# Slot.net
KiCad netlist of a schematic drawn in Altium Designer
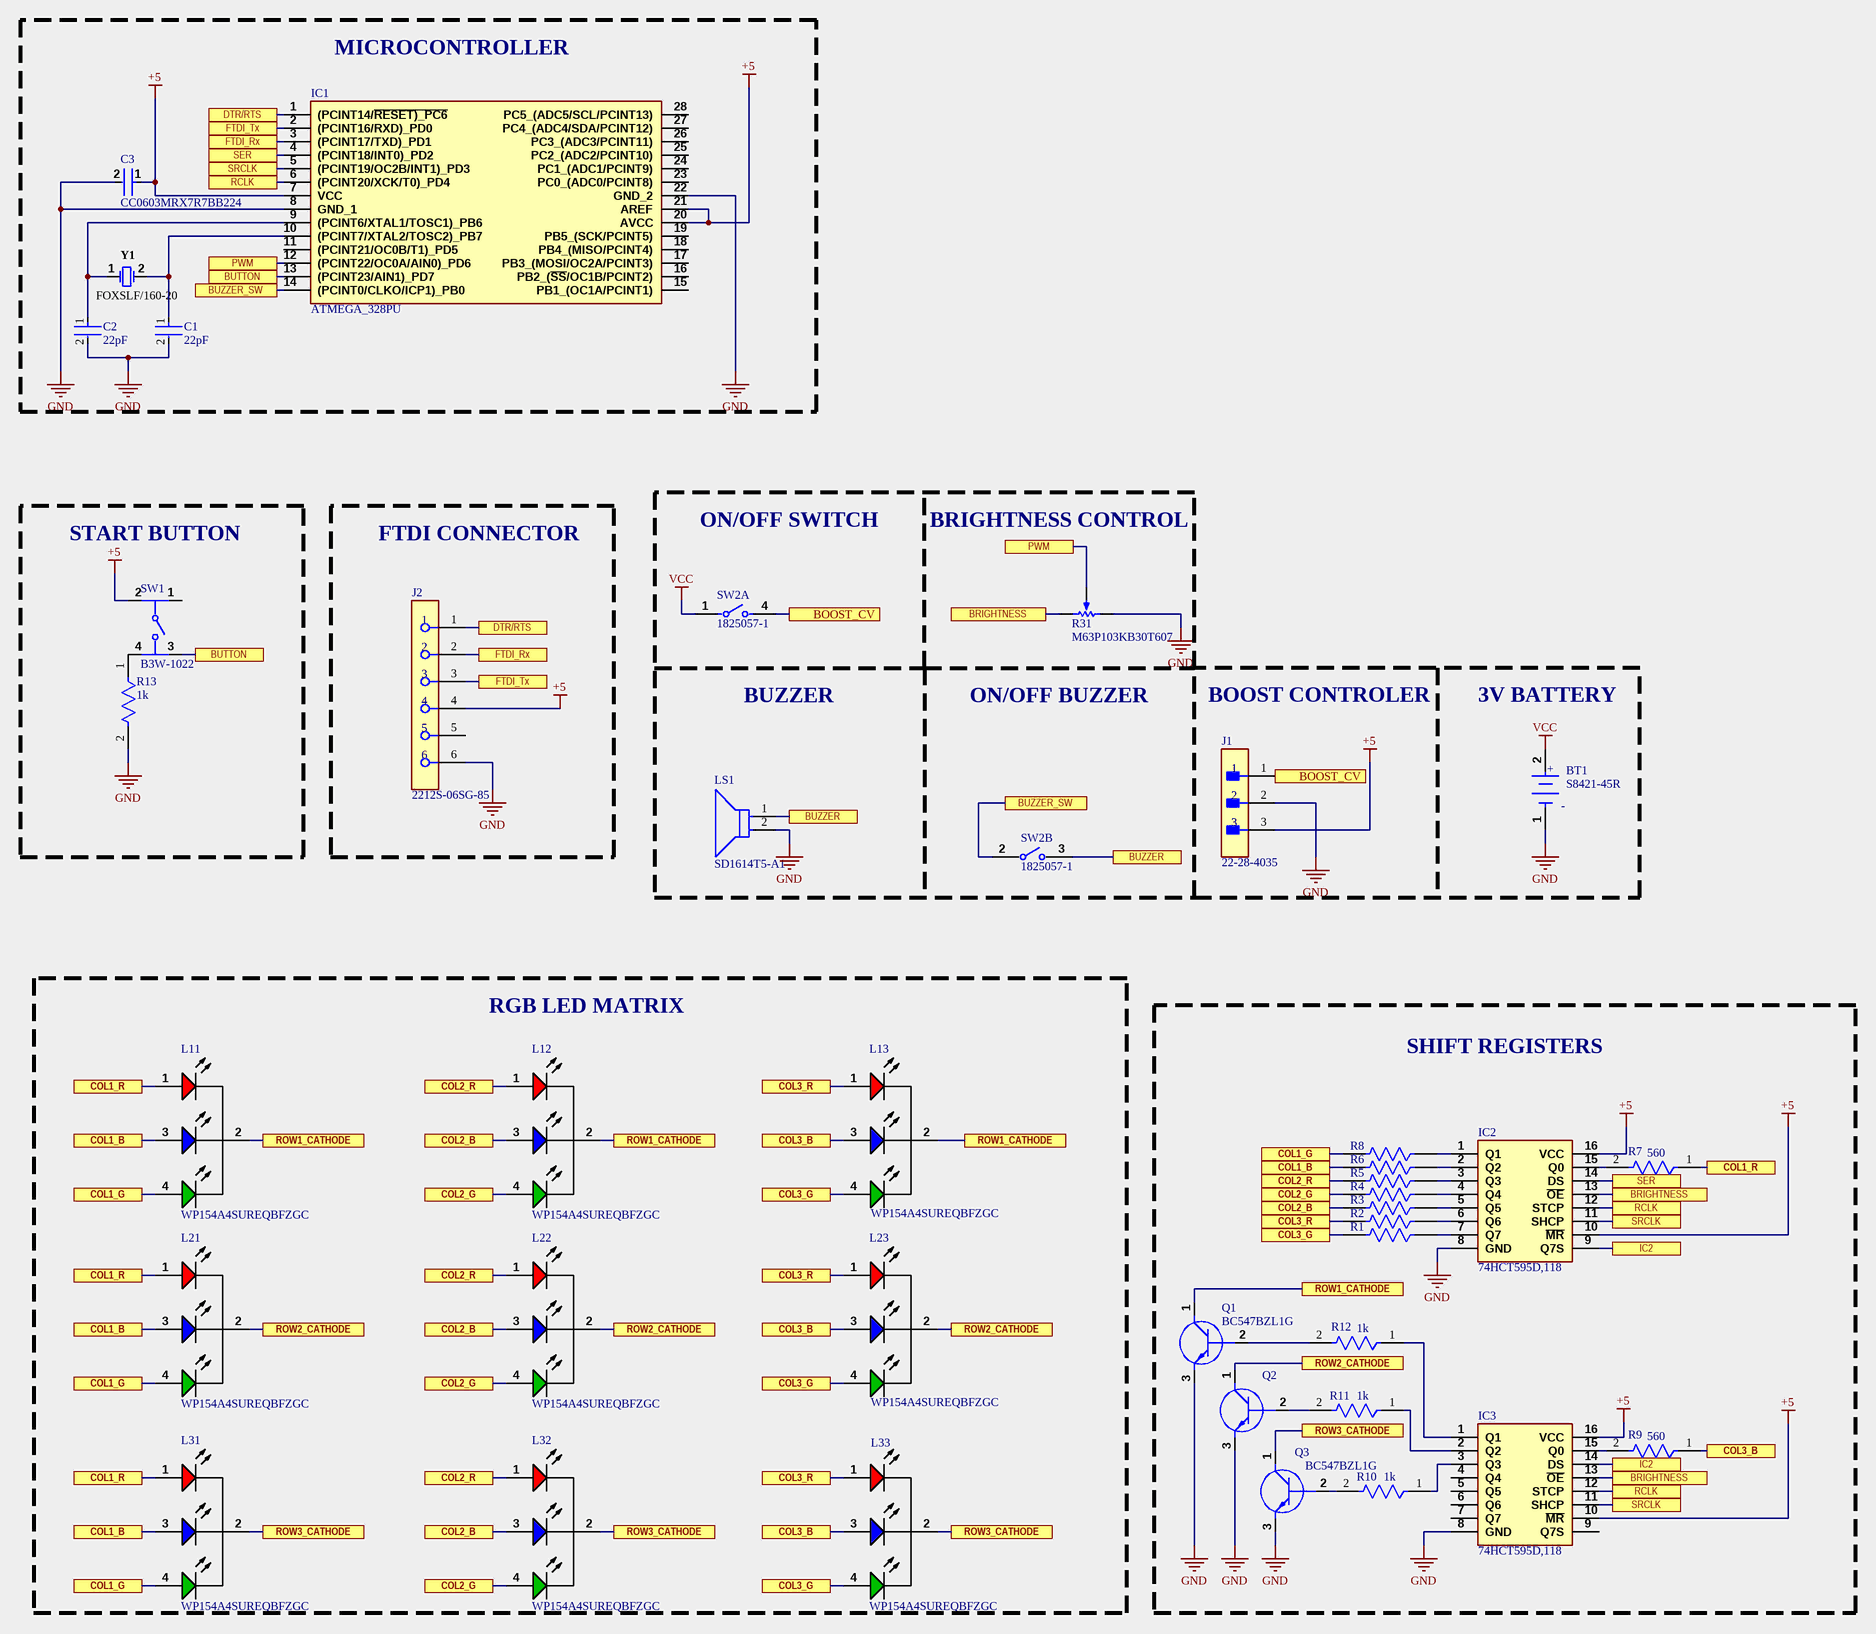
[diagram p0: Slot.SchDoc]

(export (version "E")
  (design (tool "Eeschema 10.0.6"))
  (components
    (comp (ref "BT1")
      (value "S8421-45R")
      (footprint "FP-S8421-45R-MFG")
      (description "BATTERY HOLDER COIN 20MM SMD")
      (libsource (lib "Altium Content Vault") (part "60d3b5b901a8747834971d0eb8cf3fd"))
    )
    (comp (ref "C1")
      (value "22pF")
      (footprint "FP-K221K15X7RF5TL2-MFG")
      (description "K221K15X7RF5TL2 Multilayer Ceramic Capacitor, 220 pF, 50 V, ± 10%, X7R, Radial Leaded")
      (fields (field (name "TOLERANCE") "10%"))
      (libsource (lib "Altium Content Vault") (part "b4654b650e69147ec39a6b967a45e02"))
    )
    (comp (ref "C2")
      (value "22pF")
      (footprint "FP-K221K15X7RF5TL2-MFG")
      (description "K221K15X7RF5TL2 Multilayer Ceramic Capacitor, 220 pF, 50 V, ± 10%, X7R, Radial Leaded")
      (fields (field (name "TOLERANCE") "10%"))
      (libsource (lib "Altium Content Vault") (part "b4654b650e69147ec39a6b967a45e02"))
    )
    (comp (ref "C3")
      (value "CC0603MRX7R7BB224")
      (footprint "FP-CC0603-DA-MFG")
      (description "CAP CER 0.22UF 16V X7R 0603")
      (fields (field (name "VOLTAGE") "16 V") (field (name "MANUFACTURER") "YAGEO"))
      (libsource (lib "Altium Content Vault") (part "11868f565c42a9108669ba33697ecf6"))
    )
    (comp (ref "IC1")
      (value "ATMEGA_328PU")
      (footprint "SamacSys:DIP794W56P254L3486H508Q28N")
      (description "Integrated Circuit")
      (fields (field (name "MANUFACTURER_PART_NUMBER") "ATMEGA 328PU"))
      (libsource (lib "SamacSys") (part "ATMEGA_328PU"))
    )
    (comp (ref "IC2")
      (value "74HCT595D,118")
      (footprint "SamacSys:SOIC127P600X175-16N")
      (description "Integrated Circuit")
      (fields (field (name "MOUSER PART NUMBER") "771-74HCT595D-T"))
      (libsource (lib "SamacSys") (part "74HCT595D,118"))
    )
    (comp (ref "IC3")
      (value "74HCT595D,118")
      (footprint "SamacSys:SOIC127P600X175-16N")
      (description "Integrated Circuit")
      (fields (field (name "MOUSER PART NUMBER") "771-74HCT595D-T"))
      (libsource (lib "SamacSys") (part "74HCT595D,118"))
    )
    (comp (ref "J1")
      (value "22-28-4035")
      (footprint "FP-22-28-4035-MFG")
      (libsource (lib "Altium Content Vault") (part "0d3f023dd272f625e17a2be33dea85f"))
    )
    (comp (ref "J2")
      (value "2212S-06SG-85")
      (footprint "FP-2212S-06SG-85-MFG")
      (description "Header, Rectangular, 6 Positions, Receptacle, 2.54mm pitch, Vertical, Through-Hole")
      (libsource (lib "Altium Content Vault") (part "340f86754993f25901839ab6d466df7"))
    )
    (comp (ref "L11")
      (value "WP154A4SUREQBFZGC")
      (footprint "KING-WP154A4SUREQBFZGC_V")
      (description "Full Color LED Lamp, Dominant Wavelength RGB 630 / 525 / 465 nm, -40 to 85 degC, 4-Pin THD, RoHS")
      (fields (field (name "MANUFACTURER") "Kingbright"))
      (libsource (lib "Altium Content Vault") (part "LED-RGB-AKAA-4"))
    )
    (comp (ref "L12")
      (value "WP154A4SUREQBFZGC")
      (footprint "KING-WP154A4SUREQBFZGC_V")
      (description "Full Color LED Lamp, Dominant Wavelength RGB 630 / 525 / 465 nm, -40 to 85 degC, 4-Pin THD, RoHS")
      (fields (field (name "MANUFACTURER") "Kingbright"))
      (libsource (lib "Altium Content Vault") (part "LED-RGB-AKAA-4"))
    )
    (comp (ref "L13")
      (value "WP154A4SUREQBFZGC")
      (footprint "KING-WP154A4SUREQBFZGC_V")
      (description "Full Color LED Lamp, Dominant Wavelength RGB 630 / 525 / 465 nm, -40 to 85 degC, 4-Pin THD, RoHS")
      (fields (field (name "MANUFACTURER") "Kingbright"))
      (libsource (lib "Altium Content Vault") (part "LED-RGB-AKAA-4"))
    )
    (comp (ref "L21")
      (value "WP154A4SUREQBFZGC")
      (footprint "KING-WP154A4SUREQBFZGC_V")
      (description "Full Color LED Lamp, Dominant Wavelength RGB 630 / 525 / 465 nm, -40 to 85 degC, 4-Pin THD, RoHS")
      (fields (field (name "MANUFACTURER") "Kingbright"))
      (libsource (lib "Altium Content Vault") (part "LED-RGB-AKAA-4"))
    )
    (comp (ref "L22")
      (value "WP154A4SUREQBFZGC")
      (footprint "KING-WP154A4SUREQBFZGC_V")
      (description "Full Color LED Lamp, Dominant Wavelength RGB 630 / 525 / 465 nm, -40 to 85 degC, 4-Pin THD, RoHS")
      (fields (field (name "MANUFACTURER") "Kingbright"))
      (libsource (lib "Altium Content Vault") (part "LED-RGB-AKAA-4"))
    )
    (comp (ref "L23")
      (value "WP154A4SUREQBFZGC")
      (footprint "KING-WP154A4SUREQBFZGC_V")
      (description "Full Color LED Lamp, Dominant Wavelength RGB 630 / 525 / 465 nm, -40 to 85 degC, 4-Pin THD, RoHS")
      (fields (field (name "MANUFACTURER") "Kingbright"))
      (libsource (lib "Altium Content Vault") (part "LED-RGB-AKAA-4"))
    )
    (comp (ref "L31")
      (value "WP154A4SUREQBFZGC")
      (footprint "KING-WP154A4SUREQBFZGC_V")
      (description "Full Color LED Lamp, Dominant Wavelength RGB 630 / 525 / 465 nm, -40 to 85 degC, 4-Pin THD, RoHS")
      (fields (field (name "MANUFACTURER") "Kingbright"))
      (libsource (lib "Altium Content Vault") (part "LED-RGB-AKAA-4"))
    )
    (comp (ref "L32")
      (value "WP154A4SUREQBFZGC")
      (footprint "KING-WP154A4SUREQBFZGC_V")
      (description "Full Color LED Lamp, Dominant Wavelength RGB 630 / 525 / 465 nm, -40 to 85 degC, 4-Pin THD, RoHS")
      (fields (field (name "MANUFACTURER") "Kingbright"))
      (libsource (lib "Altium Content Vault") (part "LED-RGB-AKAA-4"))
    )
    (comp (ref "L33")
      (value "WP154A4SUREQBFZGC")
      (footprint "KING-WP154A4SUREQBFZGC_V")
      (description "Full Color LED Lamp, Dominant Wavelength RGB 630 / 525 / 465 nm, -40 to 85 degC, 4-Pin THD, RoHS")
      (fields (field (name "MANUFACTURER") "Kingbright"))
      (libsource (lib "Altium Content Vault") (part "LED-RGB-AKAA-4"))
    )
    (comp (ref "LS1")
      (value "SD1614T5-A1")
      (footprint "FP-SD1614T5-A1-MFG")
      (description "BUZZER MAGNETIC 5V 80DB 2048HZ 1")
      (libsource (lib "Altium Content Vault") (part "e749a21513d54f03b70f810f265f423"))
    )
    (comp (ref "Q1")
      (value "BC547BZL1G")
      (footprint "SamacSys:BC547BZL1G")
      (description "Transistor BJT NPN")
      (fields (field (name "MOUSER PART NUMBER") "863-BC547BZL1G"))
      (libsource (lib "SamacSys") (part "BC547BZL1G"))
    )
    (comp (ref "Q2")
      (value "BC547BZL1G")
      (footprint "SamacSys:BC547BZL1G")
      (description "Transistor BJT NPN")
      (fields (field (name "MOUSER PART NUMBER") "863-BC547BZL1G"))
      (libsource (lib "SamacSys") (part "BC547BZL1G"))
    )
    (comp (ref "Q3")
      (value "BC547BZL1G")
      (footprint "SamacSys:BC547BZL1G")
      (description "Transistor BJT NPN")
      (fields (field (name "MOUSER PART NUMBER") "863-BC547BZL1G"))
      (libsource (lib "SamacSys") (part "BC547BZL1G"))
    )
    (comp (ref "R1")
      (value "560")
      (footprint "SamacSys:RESC1608X55N")
      (description "Resistor")
      (fields (field (name "MANUFACTURER_PART_NUMBER") "CPF0603B12RE"))
      (libsource (lib "") (part "CPF0603B12RE_1"))
    )
    (comp (ref "R2")
      (value "560")
      (footprint "SamacSys:RESC1608X55N")
      (description "Resistor")
      (fields (field (name "MANUFACTURER_PART_NUMBER") "CPF0603B12RE"))
      (libsource (lib "") (part "CPF0603B12RE_1"))
    )
    (comp (ref "R3")
      (value "560")
      (footprint "SamacSys:RESC1608X55N")
      (description "Resistor")
      (fields (field (name "MANUFACTURER_PART_NUMBER") "CPF0603B12RE"))
      (libsource (lib "") (part "CPF0603B12RE_1"))
    )
    (comp (ref "R4")
      (value "560")
      (footprint "SamacSys:RESC1608X55N")
      (description "Resistor")
      (fields (field (name "MANUFACTURER_PART_NUMBER") "CPF0603B12RE"))
      (libsource (lib "") (part "CPF0603B12RE_1"))
    )
    (comp (ref "R5")
      (value "560")
      (footprint "SamacSys:RESC1608X55N")
      (description "Resistor")
      (fields (field (name "MANUFACTURER_PART_NUMBER") "CPF0603B12RE"))
      (libsource (lib "") (part "CPF0603B12RE_1"))
    )
    (comp (ref "R6")
      (value "560")
      (footprint "SamacSys:RESC1608X55N")
      (description "Resistor")
      (fields (field (name "MANUFACTURER_PART_NUMBER") "CPF0603B12RE"))
      (libsource (lib "") (part "CPF0603B12RE_1"))
    )
    (comp (ref "R7")
      (value "560")
      (footprint "SamacSys:RESC1608X55N")
      (description "Resistor")
      (fields (field (name "MANUFACTURER_PART_NUMBER") "CPF0603B12RE"))
      (libsource (lib "SamacSys") (part "CPF0603B12RE"))
    )
    (comp (ref "R8")
      (value "560")
      (footprint "SamacSys:RESC1608X55N")
      (description "Resistor")
      (fields (field (name "MANUFACTURER_PART_NUMBER") "CPF0603B12RE"))
      (libsource (lib "") (part "CPF0603B12RE_1"))
    )
    (comp (ref "R9")
      (value "560")
      (footprint "SamacSys:RESC1608X55N")
      (description "Resistor")
      (fields (field (name "MANUFACTURER_PART_NUMBER") "CPF0603B12RE"))
      (libsource (lib "SamacSys") (part "CPF0603B12RE"))
    )
    (comp (ref "R10")
      (value "1k")
      (footprint "SamacSys:RESC1608X55N")
      (description "Resistor")
      (fields (field (name "MANUFACTURER_PART_NUMBER") "CPF0603B12RE"))
      (libsource (lib "SamacSys") (part "CPF0603B12RE"))
    )
    (comp (ref "R11")
      (value "1k")
      (footprint "SamacSys:RESC1608X55N")
      (description "Resistor")
      (fields (field (name "MANUFACTURER_PART_NUMBER") "CPF0603B12RE"))
      (libsource (lib "SamacSys") (part "CPF0603B12RE"))
    )
    (comp (ref "R12")
      (value "1k")
      (footprint "SamacSys:RESC1608X55N")
      (description "Resistor")
      (fields (field (name "MANUFACTURER_PART_NUMBER") "CPF0603B12RE"))
      (libsource (lib "SamacSys") (part "CPF0603B12RE"))
    )
    (comp (ref "R13")
      (value "1k")
      (footprint "SamacSys:RESC1608X55N")
      (description "Resistor")
      (fields (field (name "MANUFACTURER_PART_NUMBER") "CPF0603B12RE"))
      (libsource (lib "SamacSys") (part "CPF0603B12RE"))
    )
    (comp (ref "R31")
      (value "M63P103KB30T607")
      (footprint "VISH-M63P103KB30T607")
      (description "Single-Turn Cermet Trimmer, 10 KOhm, -55 to 125 degC, 3-Pin THD, RoHS, Bulk")
      (fields (field (name "MANUFACTURER") "Vishay Semiconductor"))
      (libsource (lib "Altium Content Vault") (part "RES-POT-3"))
    )
    (comp (ref "SW1")
      (value "B3W-1022")
      (footprint "FP-B3W-1022-MFG")
      (description "SWITCH TACTILE SPST-NO 0.05A 24V")
      (libsource (lib "Altium Content Vault") (part "b8895f3f4cefb76e1819d2863dba89b"))
    )
    (comp (ref "SW2")
      (value "1825057-1")
      (footprint "FP-1825057-1-MFG")
      (description "SWITCH SLIDE DIP SPST 100MA 24V")
      (fields
        (field (name "OCTOPART") "https://octopart.com/1825057-1-te+connectivity-46507313")
        (field (name "MANUFACTURER") "TE Connectivity")
      )
      (libsource (lib "Altium Content Vault") (part "305b8df74c9585226458c49fb7f7021"))
    )
    (comp (ref "Y1")
      (value "FOXSLF/160-20")
      (footprint "FOX-FOXSLF160-20")
      (description "Resistance Weld Thru-Hole Crystal, 16 MHz, -20 to 70 degC, 2-Pin THD, RoHS, Bulk")
      (fields (field (name "TOLERANCE") "1%"))
      (libsource (lib "Altium Content Vault") (part "XTAL-1-2-2"))
    )
  )
  (nets
    (net (code "1") (name "+5") (class "Default")
      (node (ref "C3") (pin "1") (pinfunction "1_1") (pintype "passive"))
      (node (ref "IC1") (pin "20") (pinfunction "AVCC_20") (pintype "passive"))
      (node (ref "IC1") (pin "21") (pinfunction "AREF_21") (pintype "passive"))
      (node (ref "IC1") (pin "7") (pinfunction "VCC_7") (pintype "passive"))
      (node (ref "IC2") (pin "10") (pinfunction "~{MR}_10") (pintype "passive"))
      (node (ref "IC2") (pin "16") (pinfunction "VCC_16") (pintype "passive"))
      (node (ref "IC3") (pin "10") (pinfunction "~{MR}_10") (pintype "passive"))
      (node (ref "IC3") (pin "16") (pinfunction "VCC_16") (pintype "passive"))
      (node (ref "J1") (pin "3") (pinfunction "3_3") (pintype "passive"))
      (node (ref "J2") (pin "4") (pinfunction "4_4") (pintype "passive"))
      (node (ref "SW1") (pin "2") (pinfunction "2_2") (pintype "passive"))
    )
    (net (code "2") (name "/BOOST_CV") (class "Default")
      (node (ref "J1") (pin "1") (pinfunction "1_1") (pintype "passive"))
      (node (ref "SW2") (pin "4") (pinfunction "4_4") (pintype "passive"))
    )
    (net (code "3") (name "/BRIGHTNESS") (class "Default")
      (node (ref "IC2") (pin "13") (pinfunction "~{OE}_13") (pintype "passive"))
      (node (ref "IC3") (pin "13") (pinfunction "~{OE}_13") (pintype "passive"))
      (node (ref "R31") (pin "3") (pinfunction "CW_3") (pintype "passive"))
    )
    (net (code "4") (name "/BUTTON") (class "Default")
      (node (ref "IC1") (pin "13") (pinfunction "(PCINT23/AIN1)_PD7_13") (pintype "passive"))
      (node (ref "SW1") (pin "3") (pinfunction "3_3") (pintype "passive"))
    )
    (net (code "5") (name "/BUZZER") (class "Default")
      (node (ref "LS1") (pin "1") (pinfunction "C_1") (pintype "passive"))
      (node (ref "SW2") (pin "3") (pinfunction "3_3") (pintype "passive"))
    )
    (net (code "6") (name "/BUZZER_SW") (class "Default")
      (node (ref "IC1") (pin "14") (pinfunction "(PCINT0/CLKO/ICP1)_PB0_14") (pintype "passive"))
      (node (ref "SW2") (pin "2") (pinfunction "2_2") (pintype "passive"))
    )
    (net (code "7") (name "/COL1_B") (class "Default")
      (node (ref "L11") (pin "3") (pinfunction "BLUE_3") (pintype "passive"))
      (node (ref "L21") (pin "3") (pinfunction "BLUE_3") (pintype "passive"))
      (node (ref "L31") (pin "3") (pinfunction "BLUE_3") (pintype "passive"))
      (node (ref "R6") (pin "2") (pinfunction "2_2") (pintype "passive"))
    )
    (net (code "8") (name "/COL1_G") (class "Default")
      (node (ref "L11") (pin "4") (pinfunction "GREEN_4") (pintype "passive"))
      (node (ref "L21") (pin "4") (pinfunction "GREEN_4") (pintype "passive"))
      (node (ref "L31") (pin "4") (pinfunction "GREEN_4") (pintype "passive"))
      (node (ref "R8") (pin "2") (pinfunction "2_2") (pintype "passive"))
    )
    (net (code "9") (name "/COL1_R") (class "Default")
      (node (ref "L11") (pin "1") (pinfunction "RED_1") (pintype "passive"))
      (node (ref "L21") (pin "1") (pinfunction "RED_1") (pintype "passive"))
      (node (ref "L31") (pin "1") (pinfunction "RED_1") (pintype "passive"))
      (node (ref "R7") (pin "1") (pinfunction "1_1") (pintype "passive"))
    )
    (net (code "10") (name "/COL2_B") (class "Default")
      (node (ref "L12") (pin "3") (pinfunction "BLUE_3") (pintype "passive"))
      (node (ref "L22") (pin "3") (pinfunction "BLUE_3") (pintype "passive"))
      (node (ref "L32") (pin "3") (pinfunction "BLUE_3") (pintype "passive"))
      (node (ref "R3") (pin "2") (pinfunction "2_2") (pintype "passive"))
    )
    (net (code "11") (name "/COL2_G") (class "Default")
      (node (ref "L12") (pin "4") (pinfunction "GREEN_4") (pintype "passive"))
      (node (ref "L22") (pin "4") (pinfunction "GREEN_4") (pintype "passive"))
      (node (ref "L32") (pin "4") (pinfunction "GREEN_4") (pintype "passive"))
      (node (ref "R4") (pin "2") (pinfunction "2_2") (pintype "passive"))
    )
    (net (code "12") (name "/COL2_R") (class "Default")
      (node (ref "L12") (pin "1") (pinfunction "RED_1") (pintype "passive"))
      (node (ref "L22") (pin "1") (pinfunction "RED_1") (pintype "passive"))
      (node (ref "L32") (pin "1") (pinfunction "RED_1") (pintype "passive"))
      (node (ref "R5") (pin "2") (pinfunction "2_2") (pintype "passive"))
    )
    (net (code "13") (name "/COL3_B") (class "Default")
      (node (ref "L13") (pin "3") (pinfunction "BLUE_3") (pintype "passive"))
      (node (ref "L23") (pin "3") (pinfunction "BLUE_3") (pintype "passive"))
      (node (ref "L33") (pin "3") (pinfunction "BLUE_3") (pintype "passive"))
      (node (ref "R9") (pin "1") (pinfunction "1_1") (pintype "passive"))
    )
    (net (code "14") (name "/COL3_G") (class "Default")
      (node (ref "L13") (pin "4") (pinfunction "GREEN_4") (pintype "passive"))
      (node (ref "L23") (pin "4") (pinfunction "GREEN_4") (pintype "passive"))
      (node (ref "L33") (pin "4") (pinfunction "GREEN_4") (pintype "passive"))
      (node (ref "R1") (pin "2") (pinfunction "2_2") (pintype "passive"))
    )
    (net (code "15") (name "/COL3_R") (class "Default")
      (node (ref "L13") (pin "1") (pinfunction "RED_1") (pintype "passive"))
      (node (ref "L23") (pin "1") (pinfunction "RED_1") (pintype "passive"))
      (node (ref "L33") (pin "1") (pinfunction "RED_1") (pintype "passive"))
      (node (ref "R2") (pin "2") (pinfunction "2_2") (pintype "passive"))
    )
    (net (code "16") (name "/DTR{slash}RTS") (class "Default")
      (node (ref "IC1") (pin "1") (pinfunction "(PCINT14/~{RESET)_PC6}_1") (pintype "passive"))
      (node (ref "J2") (pin "1") (pinfunction "1_1") (pintype "passive"))
    )
    (net (code "17") (name "/FTDI_Rx") (class "Default")
      (node (ref "IC1") (pin "3") (pinfunction "(PCINT17/TXD)_PD1_3") (pintype "passive"))
      (node (ref "J2") (pin "2") (pinfunction "2_2") (pintype "passive"))
    )
    (net (code "18") (name "/FTDI_Tx") (class "Default")
      (node (ref "IC1") (pin "2") (pinfunction "(PCINT16/RXD)_PD0_2") (pintype "passive"))
      (node (ref "J2") (pin "3") (pinfunction "3_3") (pintype "passive"))
    )
    (net (code "19") (name "/IC2") (class "Default")
      (node (ref "IC2") (pin "9") (pinfunction "Q7S_9") (pintype "passive"))
      (node (ref "IC3") (pin "14") (pinfunction "DS_14") (pintype "passive"))
    )
    (net (code "20") (name "/PWM") (class "Default")
      (node (ref "IC1") (pin "12") (pinfunction "(PCINT22/OC0A/AIN0)_PD6_12") (pintype "passive"))
      (node (ref "R31") (pin "2") (pinfunction "S_2") (pintype "passive"))
    )
    (net (code "21") (name "/RCLK") (class "Default")
      (node (ref "IC1") (pin "6") (pinfunction "(PCINT20/XCK/T0)_PD4_6") (pintype "passive"))
      (node (ref "IC2") (pin "12") (pinfunction "STCP_12") (pintype "passive"))
      (node (ref "IC3") (pin "12") (pinfunction "STCP_12") (pintype "passive"))
    )
    (net (code "22") (name "/ROW1_CATHODE") (class "Default")
      (node (ref "L11") (pin "2") (pinfunction "CATHODE_2") (pintype "passive"))
      (node (ref "L12") (pin "2") (pinfunction "CATHODE_2") (pintype "passive"))
      (node (ref "L13") (pin "2") (pinfunction "CATHODE_2") (pintype "passive"))
      (node (ref "Q1") (pin "1") (pinfunction "C_1") (pintype "passive"))
    )
    (net (code "23") (name "/ROW2_CATHODE") (class "Default")
      (node (ref "L21") (pin "2") (pinfunction "CATHODE_2") (pintype "passive"))
      (node (ref "L22") (pin "2") (pinfunction "CATHODE_2") (pintype "passive"))
      (node (ref "L23") (pin "2") (pinfunction "CATHODE_2") (pintype "passive"))
      (node (ref "Q2") (pin "1") (pinfunction "C_1") (pintype "passive"))
    )
    (net (code "24") (name "/ROW3_CATHODE") (class "Default")
      (node (ref "L31") (pin "2") (pinfunction "CATHODE_2") (pintype "passive"))
      (node (ref "L32") (pin "2") (pinfunction "CATHODE_2") (pintype "passive"))
      (node (ref "L33") (pin "2") (pinfunction "CATHODE_2") (pintype "passive"))
      (node (ref "Q3") (pin "1") (pinfunction "C_1") (pintype "passive"))
    )
    (net (code "25") (name "/SER") (class "Default")
      (node (ref "IC1") (pin "4") (pinfunction "(PCINT18/INT0)_PD2_4") (pintype "passive"))
      (node (ref "IC2") (pin "14") (pinfunction "DS_14") (pintype "passive"))
    )
    (net (code "26") (name "/SRCLK") (class "Default")
      (node (ref "IC1") (pin "5") (pinfunction "(PCINT19/OC2B/INT1)_PD3_5") (pintype "passive"))
      (node (ref "IC2") (pin "11") (pinfunction "SHCP_11") (pintype "passive"))
      (node (ref "IC3") (pin "11") (pinfunction "SHCP_11") (pintype "passive"))
    )
    (net (code "27") (name "GND") (class "Default")
      (node (ref "BT1") (pin "1") (pinfunction "C_1") (pintype "passive"))
      (node (ref "C1") (pin "2") (pinfunction "2_2") (pintype "passive"))
      (node (ref "C2") (pin "2") (pinfunction "2_2") (pintype "passive"))
      (node (ref "C3") (pin "2") (pinfunction "2_2") (pintype "passive"))
      (node (ref "IC1") (pin "22") (pinfunction "GND_2_22") (pintype "passive"))
      (node (ref "IC1") (pin "8") (pinfunction "GND_1_8") (pintype "passive"))
      (node (ref "IC2") (pin "8") (pinfunction "GND_8") (pintype "passive"))
      (node (ref "IC3") (pin "8") (pinfunction "GND_8") (pintype "passive"))
      (node (ref "J1") (pin "2") (pinfunction "2_2") (pintype "passive"))
      (node (ref "J2") (pin "6") (pinfunction "6_6") (pintype "passive"))
      (node (ref "LS1") (pin "2") (pinfunction "A_2") (pintype "passive"))
      (node (ref "Q1") (pin "3") (pinfunction "E_3") (pintype "passive"))
      (node (ref "Q2") (pin "3") (pinfunction "E_3") (pintype "passive"))
      (node (ref "Q3") (pin "3") (pinfunction "E_3") (pintype "passive"))
      (node (ref "R13") (pin "2") (pinfunction "2_2") (pintype "passive"))
      (node (ref "R31") (pin "1") (pinfunction "CCW_1") (pintype "passive"))
    )
    (net (code "28") (name "Net-(IC1-(PCINT6{slash}XTAL1{slash}TOSC1)_PB6)") (class "Default")
      (node (ref "C2") (pin "1") (pinfunction "1_1") (pintype "passive"))
      (node (ref "IC1") (pin "9") (pinfunction "(PCINT6/XTAL1/TOSC1)_PB6_9") (pintype "passive"))
      (node (ref "Y1") (pin "1") (pinfunction "1_1") (pintype "passive"))
    )
    (net (code "29") (name "Net-(IC1-(PCINT7{slash}XTAL2{slash}TOSC2)_PB7)") (class "Default")
      (node (ref "C1") (pin "1") (pinfunction "1_1") (pintype "passive"))
      (node (ref "IC1") (pin "10") (pinfunction "(PCINT7/XTAL2/TOSC2)_PB7_10") (pintype "passive"))
      (node (ref "Y1") (pin "2") (pinfunction "2_2") (pintype "passive"))
    )
    (net (code "30") (name "Net-(IC2-Q0)") (class "Default")
      (node (ref "IC2") (pin "15") (pinfunction "Q0_15") (pintype "passive"))
      (node (ref "R7") (pin "2") (pinfunction "2_2") (pintype "passive"))
    )
    (net (code "31") (name "Net-(IC2-Q1)") (class "Default")
      (node (ref "IC2") (pin "1") (pinfunction "Q1_1") (pintype "passive"))
      (node (ref "R8") (pin "1") (pinfunction "1_1") (pintype "passive"))
    )
    (net (code "32") (name "Net-(IC2-Q2)") (class "Default")
      (node (ref "IC2") (pin "2") (pinfunction "Q2_2") (pintype "passive"))
      (node (ref "R6") (pin "1") (pinfunction "1_1") (pintype "passive"))
    )
    (net (code "33") (name "Net-(IC2-Q3)") (class "Default")
      (node (ref "IC2") (pin "3") (pinfunction "Q3_3") (pintype "passive"))
      (node (ref "R5") (pin "1") (pinfunction "1_1") (pintype "passive"))
    )
    (net (code "34") (name "Net-(IC2-Q4)") (class "Default")
      (node (ref "IC2") (pin "4") (pinfunction "Q4_4") (pintype "passive"))
      (node (ref "R4") (pin "1") (pinfunction "1_1") (pintype "passive"))
    )
    (net (code "35") (name "Net-(IC2-Q5)") (class "Default")
      (node (ref "IC2") (pin "5") (pinfunction "Q5_5") (pintype "passive"))
      (node (ref "R3") (pin "1") (pinfunction "1_1") (pintype "passive"))
    )
    (net (code "36") (name "Net-(IC2-Q6)") (class "Default")
      (node (ref "IC2") (pin "6") (pinfunction "Q6_6") (pintype "passive"))
      (node (ref "R2") (pin "1") (pinfunction "1_1") (pintype "passive"))
    )
    (net (code "37") (name "Net-(IC2-Q7)") (class "Default")
      (node (ref "IC2") (pin "7") (pinfunction "Q7_7") (pintype "passive"))
      (node (ref "R1") (pin "1") (pinfunction "1_1") (pintype "passive"))
    )
    (net (code "38") (name "Net-(IC3-Q0)") (class "Default")
      (node (ref "IC3") (pin "15") (pinfunction "Q0_15") (pintype "passive"))
      (node (ref "R9") (pin "2") (pinfunction "2_2") (pintype "passive"))
    )
    (net (code "39") (name "Net-(IC3-Q1)") (class "Default")
      (node (ref "IC3") (pin "1") (pinfunction "Q1_1") (pintype "passive"))
      (node (ref "R12") (pin "1") (pinfunction "1_1") (pintype "passive"))
    )
    (net (code "40") (name "Net-(IC3-Q2)") (class "Default")
      (node (ref "IC3") (pin "2") (pinfunction "Q2_2") (pintype "passive"))
      (node (ref "R11") (pin "1") (pinfunction "1_1") (pintype "passive"))
    )
    (net (code "41") (name "Net-(IC3-Q3)") (class "Default")
      (node (ref "IC3") (pin "3") (pinfunction "Q3_3") (pintype "passive"))
      (node (ref "R10") (pin "1") (pinfunction "1_1") (pintype "passive"))
    )
    (net (code "42") (name "Net-(Q1-B)") (class "Default")
      (node (ref "Q1") (pin "2") (pinfunction "B_2") (pintype "passive"))
      (node (ref "R12") (pin "2") (pinfunction "2_2") (pintype "passive"))
    )
    (net (code "43") (name "Net-(Q2-B)") (class "Default")
      (node (ref "Q2") (pin "2") (pinfunction "B_2") (pintype "passive"))
      (node (ref "R11") (pin "2") (pinfunction "2_2") (pintype "passive"))
    )
    (net (code "44") (name "Net-(Q3-B)") (class "Default")
      (node (ref "Q3") (pin "2") (pinfunction "B_2") (pintype "passive"))
      (node (ref "R10") (pin "2") (pinfunction "2_2") (pintype "passive"))
    )
    (net (code "45") (name "Net-(R13-Pad1)") (class "Default")
      (node (ref "R13") (pin "1") (pinfunction "1_1") (pintype "passive"))
      (node (ref "SW1") (pin "4") (pinfunction "4_4") (pintype "passive"))
    )
    (net (code "46") (name "VCC") (class "Default")
      (node (ref "BT1") (pin "2") (pinfunction "A_2") (pintype "passive"))
      (node (ref "SW2") (pin "1") (pinfunction "1_1") (pintype "passive"))
    )
    (net (code "47") (name "unconnected-(IC1-(PCINT21{slash}OC0B{slash}T1)_PD5-Pad11)") (class "Default")
      (node (ref "IC1") (pin "11") (pinfunction "(PCINT21/OC0B/T1)_PD5_11") (pintype "passive"))
    )
    (net (code "48") (name "unconnected-(IC1-PB1_(OC1A{slash}PCINT1)-Pad15)") (class "Default")
      (node (ref "IC1") (pin "15") (pinfunction "PB1_(OC1A/PCINT1)_15") (pintype "passive"))
    )
    (net (code "49") (name "unconnected-(IC1-PB2_(~{SS}{slash}OC1B{slash}PCINT2)-Pad16)") (class "Default")
      (node (ref "IC1") (pin "16") (pinfunction "PB2_(~{SS}/OC1B/PCINT2)_16") (pintype "passive"))
    )
    (net (code "50") (name "unconnected-(IC1-PB3_(MOSI{slash}OC2A{slash}PCINT3)-Pad17)") (class "Default")
      (node (ref "IC1") (pin "17") (pinfunction "PB3_(MOSI/OC2A/PCINT3)_17") (pintype "passive"))
    )
    (net (code "51") (name "unconnected-(IC1-PB4_(MISO{slash}PCINT4)-Pad18)") (class "Default")
      (node (ref "IC1") (pin "18") (pinfunction "PB4_(MISO/PCINT4)_18") (pintype "passive"))
    )
    (net (code "52") (name "unconnected-(IC1-PB5_(SCK{slash}PCINT5)-Pad19)") (class "Default")
      (node (ref "IC1") (pin "19") (pinfunction "PB5_(SCK/PCINT5)_19") (pintype "passive"))
    )
    (net (code "53") (name "unconnected-(IC1-PC0_(ADC0{slash}PCINT8)-Pad23)") (class "Default")
      (node (ref "IC1") (pin "23") (pinfunction "PC0_(ADC0/PCINT8)_23") (pintype "passive"))
    )
    (net (code "54") (name "unconnected-(IC1-PC1_(ADC1{slash}PCINT9)-Pad24)") (class "Default")
      (node (ref "IC1") (pin "24") (pinfunction "PC1_(ADC1/PCINT9)_24") (pintype "passive"))
    )
    (net (code "55") (name "unconnected-(IC1-PC2_(ADC2{slash}PCINT10)-Pad25)") (class "Default")
      (node (ref "IC1") (pin "25") (pinfunction "PC2_(ADC2/PCINT10)_25") (pintype "passive"))
    )
    (net (code "56") (name "unconnected-(IC1-PC3_(ADC3{slash}PCINT11)-Pad26)") (class "Default")
      (node (ref "IC1") (pin "26") (pinfunction "PC3_(ADC3/PCINT11)_26") (pintype "passive"))
    )
    (net (code "57") (name "unconnected-(IC1-PC4_(ADC4{slash}SDA{slash}PCINT12)-Pad27)") (class "Default")
      (node (ref "IC1") (pin "27") (pinfunction "PC4_(ADC4/SDA/PCINT12)_27") (pintype "passive"))
    )
    (net (code "58") (name "unconnected-(IC1-PC5_(ADC5{slash}SCL{slash}PCINT13)-Pad28)") (class "Default")
      (node (ref "IC1") (pin "28") (pinfunction "PC5_(ADC5/SCL/PCINT13)_28") (pintype "passive"))
    )
    (net (code "59") (name "unconnected-(IC3-Q4-Pad4)") (class "Default")
      (node (ref "IC3") (pin "4") (pinfunction "Q4_4") (pintype "passive"))
    )
    (net (code "60") (name "unconnected-(IC3-Q5-Pad5)") (class "Default")
      (node (ref "IC3") (pin "5") (pinfunction "Q5_5") (pintype "passive"))
    )
    (net (code "61") (name "unconnected-(IC3-Q6-Pad6)") (class "Default")
      (node (ref "IC3") (pin "6") (pinfunction "Q6_6") (pintype "passive"))
    )
    (net (code "62") (name "unconnected-(IC3-Q7-Pad7)") (class "Default")
      (node (ref "IC3") (pin "7") (pinfunction "Q7_7") (pintype "passive"))
    )
    (net (code "63") (name "unconnected-(IC3-Q7S-Pad9)") (class "Default")
      (node (ref "IC3") (pin "9") (pinfunction "Q7S_9") (pintype "passive"))
    )
    (net (code "64") (name "unconnected-(J2-Pad5)") (class "Default")
      (node (ref "J2") (pin "5") (pinfunction "5_5") (pintype "passive"))
    )
    (net (code "65") (name "unconnected-(SW1-Pad1)") (class "Default")
      (node (ref "SW1") (pin "1") (pinfunction "1_1") (pintype "passive"))
    )
  )
)
